# CAN.net
KiCad netlist of a schematic drawn in Altium Designer
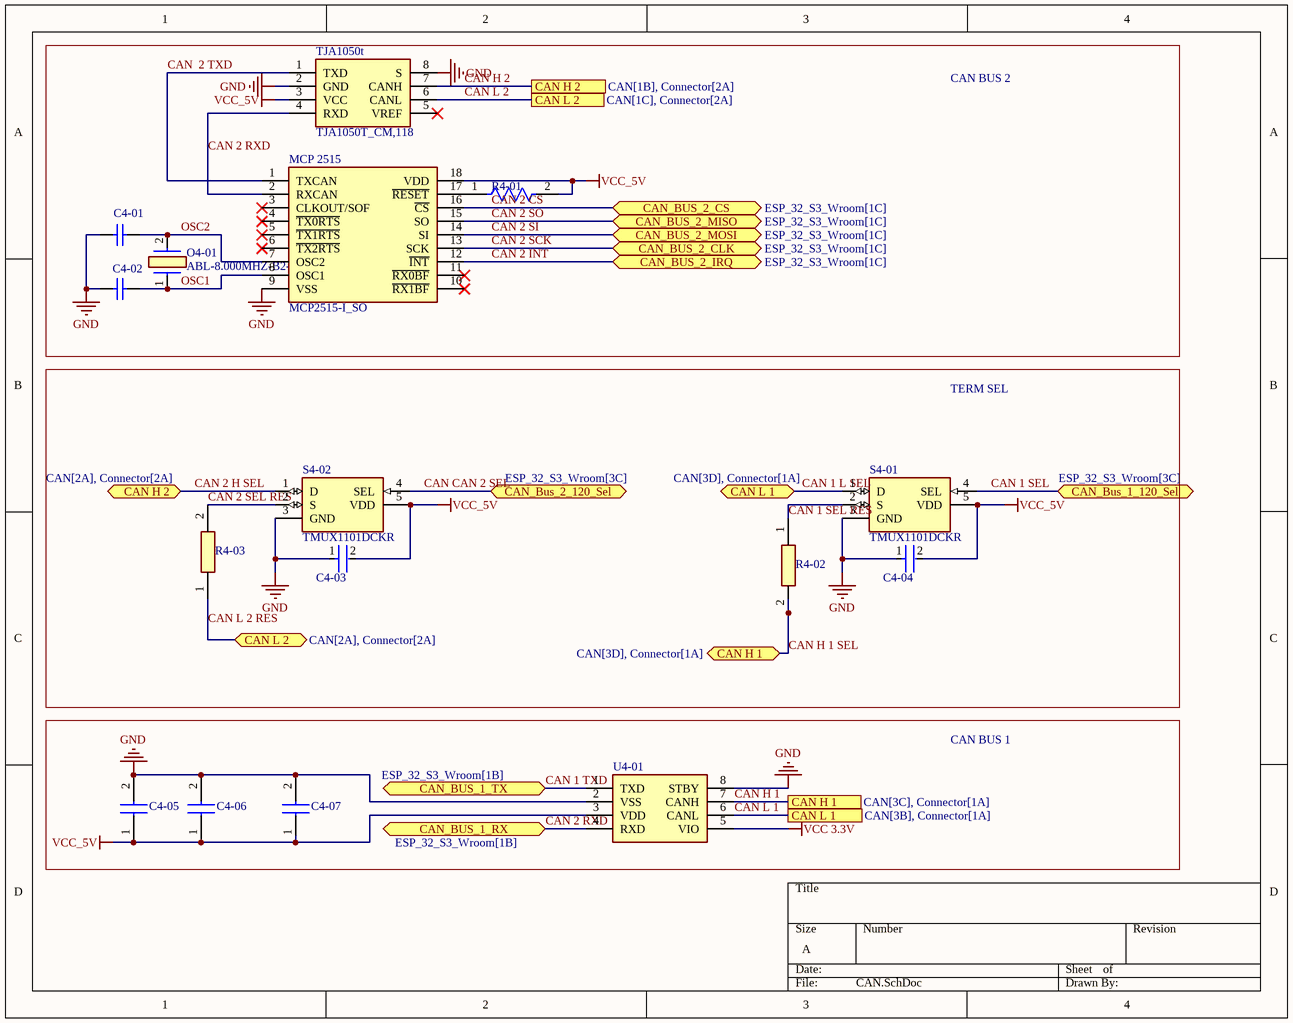
[diagram p0: CAN.SchDoc]

(export (version "E")
  (design (tool "Eeschema 10.0.6"))
  (components
    (comp (ref "C4-01")
      (value "GRM1555C1H220JA01D")
      (footprint "CAPC1005X55X25NL05T10")
      (fields (field (name "MANUFACTURER") "Murata"))
      (libsource (lib "Altium Content Vault") (part "CAP"))
    )
    (comp (ref "C4-02")
      (value "GRM1555C1H220JA01D")
      (footprint "CAPC1005X55X25NL05T10")
      (fields (field (name "MANUFACTURER") "Murata"))
      (libsource (lib "Altium Content Vault") (part "CAP"))
    )
    (comp (ref "C4-03")
      (value "GCJ21BR71H105KA01L")
      (footprint "FP-GCJ21B-0_3-IPC_B")
      (description "Multilayer Ceramic Capacitors MLCC - SMD/SMT 0805 1uF 10%, 50VDC,  X7R 15%")
      (fields (field (name "TOLERANCE") "10%"))
      (libsource (lib "Altium Content Vault") (part "02cd4be3c70576c341d710602a673aa"))
    )
    (comp (ref "C4-04")
      (value "GCJ21BR71H105KA01L")
      (footprint "FP-GCJ21B-0_3-IPC_B")
      (description "Multilayer Ceramic Capacitors MLCC - SMD/SMT 0805 1uF 10%, 50VDC,  X7R 15%")
      (fields (field (name "TOLERANCE") "10%"))
      (libsource (lib "Altium Content Vault") (part "02cd4be3c70576c341d710602a673aa"))
    )
    (comp (ref "C4-05")
      (value "CL21A226MAYNNNE")
      (footprint "SamacSys:CAPC2012X145N")
      (description "Capacitor")
      (fields (field (name "MOUSER PART NUMBER") "187-CL21A226MAYNNNE"))
      (libsource (lib "*") (part "CL21A226MAYNNNE"))
    )
    (comp (ref "C4-06")
      (value "CL21A226MAYNNNE")
      (footprint "SamacSys:CAPC2012X145N")
      (description "Capacitor")
      (fields (field (name "MOUSER PART NUMBER") "187-CL21A226MAYNNNE"))
      (libsource (lib "*") (part "CL21A226MAYNNNE"))
    )
    (comp (ref "C4-07")
      (value ".1uF")
      (footprint "SamacSys:CAPC2012X95N")
      (description "Capacitor")
      (fields
        (field (name "MANUFACTURER_PART_NUMBER") "CL21B104KBCNNNC")
        (field (name "MOUSER PART NUMBER") "187-CL21B104KBCNNNC")
      )
      (libsource (lib "*") (part "CL21B104KBCNNNC"))
    )
    (comp (ref "MCP 2515")
      (value "MCP2515-I_SO")
      (footprint "SOIC127P1030X265-18N")
      (description "Integrated Circuit")
      (fields
        (field (name "ARROW PART NUMBER") "MCP2515-I/SO")
        (field (name "MOUSER PART NUMBER") "579-MCP2515-I/SO")
      )
      (libsource (lib "Americas- Grizzlies Racing- Oakland University") (part "MCP2515-I_SO"))
    )
    (comp (ref "O4-01")
      (value "ABL-8.000MHZ-B2-T")
      (footprint "ABL")
      (description "Crystal or Oscillator")
      (fields (field (name "MOUSER PART NUMBER") "815-ABL8000MHZB2T"))
      (libsource (lib "Americas- Grizzlies Racing- Oakland University") (part "ABL-8.000MHZ-B2-T"))
    )
    (comp (ref "R4-01")
      (value "RC0603FR-0710KL")
      (footprint "FP-RC0603-0_55-IPC_C")
      (description "RES 10K OHM 1% 1/10W 0603")
      (fields (field (name "TOLERANCE") "1%"))
      (libsource (lib "Altium Content Vault") (part "1029c3af85768c4190bb7ad29bc67b5"))
    )
    (comp (ref "R4-02")
      (value "RC0603FR-07120RL")
      (footprint "RESC1608X55N")
      (description "Resistor")
      (fields (field (name "MOUSER PART NUMBER") "603-RC0603FR-07120RL"))
      (libsource (lib "Americas- Grizzlies Racing- Oakland University") (part "RN73H2ATTD8353B25"))
    )
    (comp (ref "R4-03")
      (value "RC0603FR-07120RL")
      (footprint "RESC1608X55N")
      (description "Resistor")
      (fields (field (name "MOUSER PART NUMBER") "603-RC0603FR-07120RL"))
      (libsource (lib "") (part "RN73H2ATTD8353B25_1"))
    )
    (comp (ref "S4-01")
      (value "TMUX1101DCKR")
      (footprint "SOT65P210X110-5N")
      (description "Switch")
      (fields (field (name "MOUSER PART NUMBER") "595-TMUX1101DCKR"))
      (libsource (lib "Americas- Grizzlies Racing- Oakland University") (part "TMUX1101DCKR"))
    )
    (comp (ref "S4-02")
      (value "TMUX1101DCKR")
      (footprint "SOT65P210X110-5N")
      (description "Switch")
      (fields (field (name "MOUSER PART NUMBER") "595-TMUX1101DCKR"))
      (libsource (lib "Americas- Grizzlies Racing- Oakland University") (part "TMUX1101DCKR"))
    )
    (comp (ref "TJA1050t")
      (value "TJA1050T_CM,118")
      (footprint "SOIC127P600X175-8N")
      (description "Integrated Circuit")
      (fields
        (field (name "ARROW PART NUMBER") "TJA1050T/CM,118")
        (field (name "MOUSER PART NUMBER") "771-TJA1050T/CM118")
      )
      (libsource (lib "Americas- Grizzlies Racing- Oakland University") (part "TJA1050T_CM,118"))
    )
    (comp (ref "U4-01")
      (value "MCP2562FD-H_SN")
      (footprint "SamacSys:SOIC127P600X175-8N")
      (description "Integrated Circuit")
      (fields
        (field (name "MANUFACTURER_PART_NUMBER") "MCP2562FD-H/SN")
        (field (name "MOUSER PART NUMBER") "579-MCP2562FD-H/SN")
      )
      (libsource (lib "*") (part "MCP2562FD-H_SN"))
    )
  )
  (nets
    (net (code "2") (name "/CAN  2 TXD") (class "Default")
      (node (ref "MCP 2515") (pin "1") (pinfunction "TXCAN_1") (pintype "passive"))
      (node (ref "TJA1050t") (pin "1") (pinfunction "TXD_1") (pintype "passive"))
    )
    (net (code "3") (name "/CAN 1 L SEL") (class "Default")
      (node (ref "S4-01") (pin "1") (pinfunction "D_1") (pintype "bidirectional"))
      (node (ref "U4-01") (pin "6") (pinfunction "CANL_6") (pintype "passive"))
    )
    (net (code "4") (name "/CAN 1 SEL") (class "Default")
      (node (ref "S4-01") (pin "4") (pinfunction "SEL_4") (pintype "input"))
    )
    (net (code "5") (name "/CAN 1 SEL RES") (class "Default")
      (node (ref "R4-02") (pin "1") (pinfunction "1_1") (pintype "passive"))
      (node (ref "S4-01") (pin "2") (pinfunction "S_2") (pintype "bidirectional"))
    )
    (net (code "6") (name "/CAN 1 TXD") (class "Default")
      (node (ref "U4-01") (pin "1") (pinfunction "TXD_1") (pintype "passive"))
    )
    (net (code "7") (name "/CAN 2 CS") (class "Default")
      (node (ref "MCP 2515") (pin "16") (pinfunction "~{CS}_16") (pintype "passive"))
    )
    (net (code "8") (name "/CAN 2 H SEL") (class "Default")
      (node (ref "S4-02") (pin "1") (pinfunction "D_1") (pintype "bidirectional"))
      (node (ref "TJA1050t") (pin "7") (pinfunction "CANH_7") (pintype "passive"))
    )
    (net (code "9") (name "/CAN 2 INT") (class "Default")
      (node (ref "MCP 2515") (pin "12") (pinfunction "~{INT}_12") (pintype "passive"))
    )
    (net (code "10") (name "/CAN 2 RXD") (class "Default")
      (node (ref "MCP 2515") (pin "2") (pinfunction "RXCAN_2") (pintype "passive"))
      (node (ref "TJA1050t") (pin "4") (pinfunction "RXD_4") (pintype "passive"))
      (node (ref "U4-01") (pin "4") (pinfunction "RXD_4") (pintype "passive"))
    )
    (net (code "11") (name "/CAN 2 SCK") (class "Default")
      (node (ref "MCP 2515") (pin "13") (pinfunction "SCK_13") (pintype "passive"))
    )
    (net (code "12") (name "/CAN 2 SEL RES") (class "Default")
      (node (ref "R4-03") (pin "2") (pinfunction "2_2") (pintype "passive"))
      (node (ref "S4-02") (pin "2") (pinfunction "S_2") (pintype "bidirectional"))
    )
    (net (code "13") (name "/CAN 2 SI") (class "Default")
      (node (ref "MCP 2515") (pin "14") (pinfunction "SI_14") (pintype "passive"))
    )
    (net (code "14") (name "/CAN 2 SO") (class "Default")
      (node (ref "MCP 2515") (pin "15") (pinfunction "SO_15") (pintype "passive"))
    )
    (net (code "15") (name "/CAN CAN 2 SEL") (class "Default")
      (node (ref "S4-02") (pin "4") (pinfunction "SEL_4") (pintype "input"))
    )
    (net (code "16") (name "/CAN H 1") (class "Default")
      (node (ref "R4-02") (pin "2") (pinfunction "2_2") (pintype "passive"))
      (node (ref "U4-01") (pin "7") (pinfunction "CANH_7") (pintype "passive"))
    )
    (net (code "17") (name "/CAN L 2") (class "Default")
      (node (ref "R4-03") (pin "1") (pinfunction "1_1") (pintype "passive"))
      (node (ref "TJA1050t") (pin "6") (pinfunction "CANL_6") (pintype "passive"))
    )
    (net (code "18") (name "/OSC1") (class "Default")
      (node (ref "C4-02") (pin "2") (pinfunction "2_2") (pintype "passive"))
      (node (ref "MCP 2515") (pin "8") (pinfunction "OSC1_8") (pintype "passive"))
      (node (ref "O4-01") (pin "1") (pinfunction "1_1") (pintype "passive"))
    )
    (net (code "19") (name "/OSC2") (class "Default")
      (node (ref "C4-01") (pin "2") (pinfunction "2_2") (pintype "passive"))
      (node (ref "MCP 2515") (pin "7") (pinfunction "OSC2_7") (pintype "passive"))
      (node (ref "O4-01") (pin "2") (pinfunction "2_2") (pintype "passive"))
    )
    (net (code "20") (name "GND") (class "Default")
      (node (ref "C4-01") (pin "1") (pinfunction "1_1") (pintype "passive"))
      (node (ref "C4-02") (pin "1") (pinfunction "1_1") (pintype "passive"))
      (node (ref "C4-03") (pin "1") (pinfunction "1_1") (pintype "passive"))
      (node (ref "C4-04") (pin "1") (pinfunction "1_1") (pintype "passive"))
      (node (ref "C4-05") (pin "2") (pinfunction "2_2") (pintype "passive"))
      (node (ref "C4-06") (pin "2") (pinfunction "2_2") (pintype "passive"))
      (node (ref "C4-07") (pin "2") (pinfunction "2_2") (pintype "passive"))
      (node (ref "MCP 2515") (pin "9") (pinfunction "VSS_9") (pintype "passive"))
      (node (ref "S4-01") (pin "3") (pinfunction "GND_3") (pintype "power_in"))
      (node (ref "S4-02") (pin "3") (pinfunction "GND_3") (pintype "power_in"))
      (node (ref "TJA1050t") (pin "2") (pinfunction "GND_2") (pintype "passive"))
      (node (ref "TJA1050t") (pin "8") (pinfunction "S_8") (pintype "passive"))
      (node (ref "U4-01") (pin "2") (pinfunction "VSS_2") (pintype "passive"))
      (node (ref "U4-01") (pin "8") (pinfunction "STBY_8") (pintype "passive"))
    )
    (net (code "21") (name "Net-(MCP 2515-~{RESET})") (class "Default")
      (node (ref "MCP 2515") (pin "17") (pinfunction "~{RESET}_17") (pintype "passive"))
      (node (ref "R4-01") (pin "1") (pinfunction "1_1") (pintype "passive"))
    )
    (net (code "22") (name "VCC 3.3V") (class "Default")
      (node (ref "U4-01") (pin "5") (pinfunction "VIO_5") (pintype "passive"))
    )
    (net (code "23") (name "VCC_5V") (class "Default")
      (node (ref "C4-03") (pin "2") (pinfunction "2_2") (pintype "passive"))
      (node (ref "C4-04") (pin "2") (pinfunction "2_2") (pintype "passive"))
      (node (ref "C4-05") (pin "1") (pinfunction "1_1") (pintype "passive"))
      (node (ref "C4-06") (pin "1") (pinfunction "1_1") (pintype "passive"))
      (node (ref "C4-07") (pin "1") (pinfunction "1_1") (pintype "passive"))
      (node (ref "MCP 2515") (pin "18") (pinfunction "VDD_18") (pintype "passive"))
      (node (ref "R4-01") (pin "2") (pinfunction "2_2") (pintype "passive"))
      (node (ref "S4-01") (pin "5") (pinfunction "VDD_5") (pintype "power_in"))
      (node (ref "S4-02") (pin "5") (pinfunction "VDD_5") (pintype "power_in"))
      (node (ref "TJA1050t") (pin "3") (pinfunction "VCC_3") (pintype "passive"))
      (node (ref "U4-01") (pin "3") (pinfunction "VDD_3") (pintype "passive"))
    )
    (net (code "24") (name "unconnected-(MCP 2515-CLKOUT{slash}SOF-Pad3)") (class "Default")
      (node (ref "MCP 2515") (pin "3") (pinfunction "CLKOUT/SOF_3") (pintype "passive+no_connect"))
    )
    (net (code "25") (name "unconnected-(MCP 2515-~{RX0BF}-Pad11)") (class "Default")
      (node (ref "MCP 2515") (pin "11") (pinfunction "~{RX0BF}_11") (pintype "passive+no_connect"))
    )
    (net (code "26") (name "unconnected-(MCP 2515-~{RX1BF}-Pad10)") (class "Default")
      (node (ref "MCP 2515") (pin "10") (pinfunction "~{RX1BF}_10") (pintype "passive+no_connect"))
    )
    (net (code "27") (name "unconnected-(MCP 2515-~{TX0RTS}-Pad4)") (class "Default")
      (node (ref "MCP 2515") (pin "4") (pinfunction "~{TX0RTS}_4") (pintype "passive+no_connect"))
    )
    (net (code "28") (name "unconnected-(MCP 2515-~{TX1RTS}-Pad5)") (class "Default")
      (node (ref "MCP 2515") (pin "5") (pinfunction "~{TX1RTS}_5") (pintype "passive+no_connect"))
    )
    (net (code "29") (name "unconnected-(MCP 2515-~{TX2RTS}-Pad6)") (class "Default")
      (node (ref "MCP 2515") (pin "6") (pinfunction "~{TX2RTS}_6") (pintype "passive+no_connect"))
    )
    (net (code "30") (name "unconnected-(TJA1050t-VREF-Pad5)") (class "Default")
      (node (ref "TJA1050t") (pin "5") (pinfunction "VREF_5") (pintype "passive+no_connect"))
    )
  )
)
